# Timer-Ruler_v2.net
KiCad netlist of a schematic drawn in EAGLE
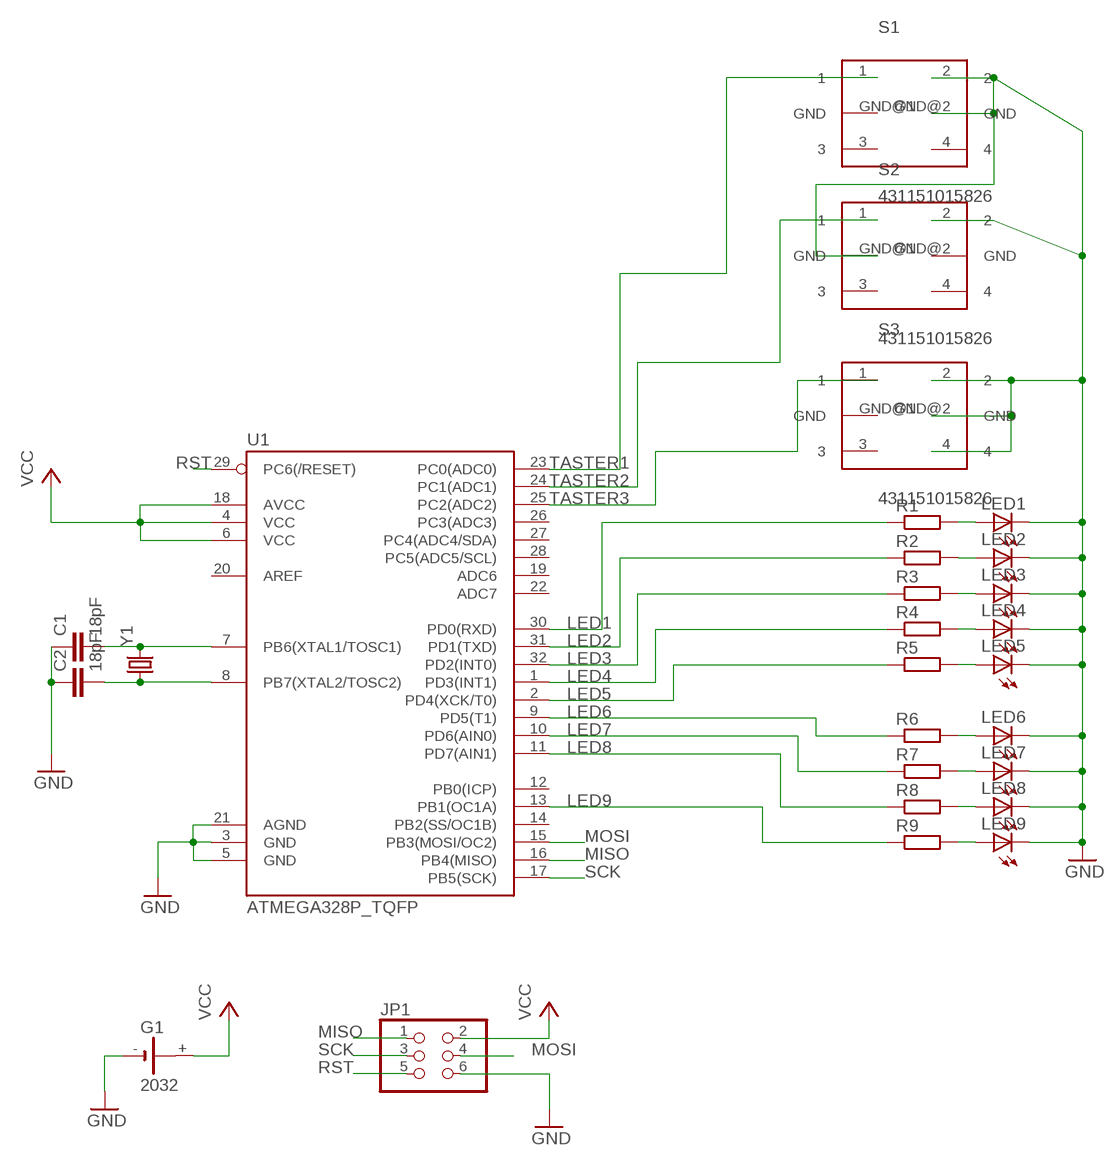
[diagram p0: schematic, sheet 1]

(export (version "E")
  (design (tool "Eeschema 10.0.6"))
  (components
    (comp (ref "C1")
      (value "18pF")
      (footprint "eagle-import:C0805K")
      (libsource (lib "eagle-import") (part "C-EUC0805K"))
    )
    (comp (ref "C2")
      (value "18pF")
      (footprint "eagle-import:C0805K")
      (libsource (lib "eagle-import") (part "C-EUC0805K"))
    )
    (comp (ref "G1")
      (value "2032")
      (footprint "eagle-import:KZH20SMD")
      (libsource (lib "eagle-import") (part "2032"))
    )
    (comp (ref "JP1")
      (value "PINHD-2X3")
      (footprint "eagle-import:2X03")
      (libsource (lib "eagle-import") (part "PINHD-2X3"))
    )
    (comp (ref "LED1")
      (value "LEDCHIP-LED0805")
      (footprint "eagle-import:CHIP-LED0805")
      (libsource (lib "eagle-import") (part "LEDCHIP-LED0805"))
    )
    (comp (ref "LED2")
      (value "LEDCHIP-LED0805")
      (footprint "eagle-import:CHIP-LED0805")
      (libsource (lib "eagle-import") (part "LEDCHIP-LED0805"))
    )
    (comp (ref "LED3")
      (value "LEDCHIP-LED0805")
      (footprint "eagle-import:CHIP-LED0805")
      (libsource (lib "eagle-import") (part "LEDCHIP-LED0805"))
    )
    (comp (ref "LED4")
      (value "LEDCHIP-LED0805")
      (footprint "eagle-import:CHIP-LED0805")
      (libsource (lib "eagle-import") (part "LEDCHIP-LED0805"))
    )
    (comp (ref "LED5")
      (value "LEDCHIP-LED0805")
      (footprint "eagle-import:CHIP-LED0805")
      (libsource (lib "eagle-import") (part "LEDCHIP-LED0805"))
    )
    (comp (ref "LED6")
      (value "LEDCHIP-LED0805")
      (footprint "eagle-import:CHIP-LED0805")
      (libsource (lib "eagle-import") (part "LEDCHIP-LED0805"))
    )
    (comp (ref "LED7")
      (value "LEDCHIP-LED0805")
      (footprint "eagle-import:CHIP-LED0805")
      (libsource (lib "eagle-import") (part "LEDCHIP-LED0805"))
    )
    (comp (ref "LED8")
      (value "LEDCHIP-LED0805")
      (footprint "eagle-import:CHIP-LED0805")
      (libsource (lib "eagle-import") (part "LEDCHIP-LED0805"))
    )
    (comp (ref "LED9")
      (value "LEDCHIP-LED0805")
      (footprint "eagle-import:CHIP-LED0805")
      (libsource (lib "eagle-import") (part "LEDCHIP-LED0805"))
    )
    (comp (ref "R1")
      (value "R-EU_R0805")
      (footprint "eagle-import:R0805")
      (libsource (lib "eagle-import") (part "R-EU_R0805"))
    )
    (comp (ref "R2")
      (value "R-EU_R0805")
      (footprint "eagle-import:R0805")
      (libsource (lib "eagle-import") (part "R-EU_R0805"))
    )
    (comp (ref "R3")
      (value "R-EU_R0805")
      (footprint "eagle-import:R0805")
      (libsource (lib "eagle-import") (part "R-EU_R0805"))
    )
    (comp (ref "R4")
      (value "R-EU_R0805")
      (footprint "eagle-import:R0805")
      (libsource (lib "eagle-import") (part "R-EU_R0805"))
    )
    (comp (ref "R5")
      (value "R-EU_R0805")
      (footprint "eagle-import:R0805")
      (libsource (lib "eagle-import") (part "R-EU_R0805"))
    )
    (comp (ref "R6")
      (value "R-EU_R0805")
      (footprint "eagle-import:R0805")
      (libsource (lib "eagle-import") (part "R-EU_R0805"))
    )
    (comp (ref "R7")
      (value "R-EU_R0805")
      (footprint "eagle-import:R0805")
      (libsource (lib "eagle-import") (part "R-EU_R0805"))
    )
    (comp (ref "R8")
      (value "R-EU_R0805")
      (footprint "eagle-import:R0805")
      (libsource (lib "eagle-import") (part "R-EU_R0805"))
    )
    (comp (ref "R9")
      (value "R-EU_R0805")
      (footprint "eagle-import:R0805")
      (libsource (lib "eagle-import") (part "R-EU_R0805"))
    )
    (comp (ref "S1")
      (value "431151015826")
      (footprint "eagle-import:431181015816")
      (libsource (lib "eagle-import") (part "431151015826"))
    )
    (comp (ref "S2")
      (value "431151015826")
      (footprint "eagle-import:431181015816")
      (libsource (lib "eagle-import") (part "431151015826"))
    )
    (comp (ref "S3")
      (value "431151015826")
      (footprint "eagle-import:431181015816")
      (libsource (lib "eagle-import") (part "431151015826"))
    )
    (comp (ref "U1")
      (value "ATMEGA328P_TQFP")
      (footprint "eagle-import:TQFP32-08")
      (libsource (lib "eagle-import") (part "ATMEGA328P_TQFP"))
    )
    (comp (ref "Y1")
      (value "CRYSTALSMD")
      (footprint "eagle-import:HC49UP")
      (libsource (lib "eagle-import") (part "CRYSTALSMD"))
    )
  )
  (nets
    (net (code "1") (name "/LED1") (class "Default")
      (node (ref "R1") (pin "1") (pinfunction "1_1") (pintype "passive"))
      (node (ref "U1") (pin "30") (pinfunction "PD0(RXD)_30") (pintype "bidirectional"))
    )
    (net (code "2") (name "/LED2") (class "Default")
      (node (ref "R2") (pin "1") (pinfunction "1_1") (pintype "passive"))
      (node (ref "U1") (pin "31") (pinfunction "PD1(TXD)_31") (pintype "bidirectional"))
    )
    (net (code "3") (name "/LED3") (class "Default")
      (node (ref "R3") (pin "1") (pinfunction "1_1") (pintype "passive"))
      (node (ref "U1") (pin "32") (pinfunction "PD2(INT0)_32") (pintype "bidirectional"))
    )
    (net (code "4") (name "/LED4") (class "Default")
      (node (ref "R4") (pin "1") (pinfunction "1_1") (pintype "passive"))
      (node (ref "U1") (pin "1") (pinfunction "PD3(INT1)_1") (pintype "bidirectional"))
    )
    (net (code "5") (name "/LED5") (class "Default")
      (node (ref "R5") (pin "1") (pinfunction "1_1") (pintype "passive"))
      (node (ref "U1") (pin "2") (pinfunction "PD4(XCK/T0)_2") (pintype "bidirectional"))
    )
    (net (code "6") (name "/LED6") (class "Default")
      (node (ref "R6") (pin "1") (pinfunction "1_1") (pintype "passive"))
      (node (ref "U1") (pin "9") (pinfunction "PD5(T1)_9") (pintype "bidirectional"))
    )
    (net (code "7") (name "/LED7") (class "Default")
      (node (ref "R7") (pin "1") (pinfunction "1_1") (pintype "passive"))
      (node (ref "U1") (pin "10") (pinfunction "PD6(AIN0)_10") (pintype "bidirectional"))
    )
    (net (code "8") (name "/LED8") (class "Default")
      (node (ref "R8") (pin "1") (pinfunction "1_1") (pintype "passive"))
      (node (ref "U1") (pin "11") (pinfunction "PD7(AIN1)_11") (pintype "bidirectional"))
    )
    (net (code "9") (name "/LED9") (class "Default")
      (node (ref "R9") (pin "1") (pinfunction "1_1") (pintype "passive"))
      (node (ref "U1") (pin "13") (pinfunction "PB1(OC1A)_13") (pintype "bidirectional"))
    )
    (net (code "10") (name "/MISO") (class "Default")
      (node (ref "JP1") (pin "1") (pinfunction "1_1") (pintype "passive"))
      (node (ref "U1") (pin "16") (pinfunction "PB4(MISO)_16") (pintype "bidirectional"))
    )
    (net (code "11") (name "/MOSI") (class "Default")
      (node (ref "JP1") (pin "4") (pinfunction "4_4") (pintype "passive"))
      (node (ref "U1") (pin "15") (pinfunction "PB3(MOSI/OC2)_15") (pintype "bidirectional"))
    )
    (net (code "12") (name "/RST") (class "Default")
      (node (ref "JP1") (pin "5") (pinfunction "5_5") (pintype "passive"))
      (node (ref "U1") (pin "29") (pinfunction "PC6(/RESET)_29") (pintype "bidirectional"))
    )
    (net (code "13") (name "/SCK") (class "Default")
      (node (ref "JP1") (pin "3") (pinfunction "3_3") (pintype "passive"))
      (node (ref "U1") (pin "17") (pinfunction "PB5(SCK)_17") (pintype "bidirectional"))
    )
    (net (code "14") (name "/TASTER1") (class "Default")
      (node (ref "S1") (pin "1") (pinfunction "1_1") (pintype "bidirectional"))
      (node (ref "U1") (pin "23") (pinfunction "PC0(ADC0)_23") (pintype "bidirectional"))
    )
    (net (code "15") (name "/TASTER2") (class "Default")
      (node (ref "S2") (pin "1") (pinfunction "1_1") (pintype "bidirectional"))
      (node (ref "U1") (pin "24") (pinfunction "PC1(ADC1)_24") (pintype "bidirectional"))
    )
    (net (code "16") (name "/TASTER3") (class "Default")
      (node (ref "S3") (pin "1") (pinfunction "1_1") (pintype "bidirectional"))
      (node (ref "U1") (pin "25") (pinfunction "PC2(ADC2)_25") (pintype "bidirectional"))
    )
    (net (code "17") (name "GND") (class "Default")
      (node (ref "C1") (pin "1") (pinfunction "1_1") (pintype "passive"))
      (node (ref "C2") (pin "1") (pinfunction "1_1") (pintype "passive"))
      (node (ref "G1") (pin "-") (pinfunction "-_-") (pintype "passive"))
      (node (ref "JP1") (pin "6") (pinfunction "6_6") (pintype "passive"))
      (node (ref "LED1") (pin "C") (pinfunction "C_C") (pintype "passive"))
      (node (ref "LED2") (pin "C") (pinfunction "C_C") (pintype "passive"))
      (node (ref "LED3") (pin "C") (pinfunction "C_C") (pintype "passive"))
      (node (ref "LED4") (pin "C") (pinfunction "C_C") (pintype "passive"))
      (node (ref "LED5") (pin "C") (pinfunction "C_C") (pintype "passive"))
      (node (ref "LED6") (pin "C") (pinfunction "C_C") (pintype "passive"))
      (node (ref "LED7") (pin "C") (pinfunction "C_C") (pintype "passive"))
      (node (ref "LED8") (pin "C") (pinfunction "C_C") (pintype "passive"))
      (node (ref "LED9") (pin "C") (pinfunction "C_C") (pintype "passive"))
      (node (ref "S1") (pin "2") (pinfunction "2_2") (pintype "bidirectional"))
      (node (ref "S1") (pin "GND@2") (pinfunction "GND_GND@2") (pintype "bidirectional"))
      (node (ref "S2") (pin "2") (pinfunction "2_2") (pintype "bidirectional"))
      (node (ref "S2") (pin "GND@1") (pinfunction "GND_GND@1") (pintype "bidirectional"))
      (node (ref "S3") (pin "2") (pinfunction "2_2") (pintype "bidirectional"))
      (node (ref "S3") (pin "4") (pinfunction "4_4") (pintype "bidirectional"))
      (node (ref "S3") (pin "GND@2") (pinfunction "GND_GND@2") (pintype "bidirectional"))
      (node (ref "U1") (pin "21") (pinfunction "AGND_21") (pintype "bidirectional"))
      (node (ref "U1") (pin "3") (pinfunction "GND_3") (pintype "bidirectional"))
      (node (ref "U1") (pin "5") (pinfunction "GND_5") (pintype "bidirectional"))
    )
    (net (code "18") (name "Net-(LED1-PadA)") (class "Default")
      (node (ref "LED1") (pin "A") (pinfunction "A_A") (pintype "passive"))
      (node (ref "R1") (pin "2") (pinfunction "2_2") (pintype "passive"))
    )
    (net (code "19") (name "Net-(LED2-PadA)") (class "Default")
      (node (ref "LED2") (pin "A") (pinfunction "A_A") (pintype "passive"))
      (node (ref "R2") (pin "2") (pinfunction "2_2") (pintype "passive"))
    )
    (net (code "20") (name "Net-(LED3-PadA)") (class "Default")
      (node (ref "LED3") (pin "A") (pinfunction "A_A") (pintype "passive"))
      (node (ref "R3") (pin "2") (pinfunction "2_2") (pintype "passive"))
    )
    (net (code "21") (name "Net-(LED4-PadA)") (class "Default")
      (node (ref "LED4") (pin "A") (pinfunction "A_A") (pintype "passive"))
      (node (ref "R4") (pin "2") (pinfunction "2_2") (pintype "passive"))
    )
    (net (code "22") (name "Net-(LED5-PadA)") (class "Default")
      (node (ref "LED5") (pin "A") (pinfunction "A_A") (pintype "passive"))
      (node (ref "R5") (pin "2") (pinfunction "2_2") (pintype "passive"))
    )
    (net (code "23") (name "Net-(LED6-PadA)") (class "Default")
      (node (ref "LED6") (pin "A") (pinfunction "A_A") (pintype "passive"))
      (node (ref "R6") (pin "2") (pinfunction "2_2") (pintype "passive"))
    )
    (net (code "24") (name "Net-(LED7-PadA)") (class "Default")
      (node (ref "LED7") (pin "A") (pinfunction "A_A") (pintype "passive"))
      (node (ref "R7") (pin "2") (pinfunction "2_2") (pintype "passive"))
    )
    (net (code "25") (name "Net-(LED8-PadA)") (class "Default")
      (node (ref "LED8") (pin "A") (pinfunction "A_A") (pintype "passive"))
      (node (ref "R8") (pin "2") (pinfunction "2_2") (pintype "passive"))
    )
    (net (code "26") (name "Net-(LED9-PadA)") (class "Default")
      (node (ref "LED9") (pin "A") (pinfunction "A_A") (pintype "passive"))
      (node (ref "R9") (pin "2") (pinfunction "2_2") (pintype "passive"))
    )
    (net (code "27") (name "Net-(U1-PB6(XTAL1{slash}TOSC1))") (class "Default")
      (node (ref "C1") (pin "2") (pinfunction "2_2") (pintype "passive"))
      (node (ref "U1") (pin "7") (pinfunction "PB6(XTAL1/TOSC1)_7") (pintype "bidirectional"))
      (node (ref "Y1") (pin "2") (pinfunction "2_2") (pintype "passive"))
    )
    (net (code "28") (name "Net-(U1-PB7(XTAL2{slash}TOSC2))") (class "Default")
      (node (ref "C2") (pin "2") (pinfunction "2_2") (pintype "passive"))
      (node (ref "U1") (pin "8") (pinfunction "PB7(XTAL2/TOSC2)_8") (pintype "bidirectional"))
      (node (ref "Y1") (pin "1") (pinfunction "1_1") (pintype "passive"))
    )
    (net (code "29") (name "VCC") (class "Default")
      (node (ref "G1") (pin "+") (pinfunction "+_+") (pintype "passive"))
      (node (ref "JP1") (pin "2") (pinfunction "2_2") (pintype "passive"))
      (node (ref "U1") (pin "18") (pinfunction "AVCC_18") (pintype "bidirectional"))
      (node (ref "U1") (pin "4") (pinfunction "VCC_4") (pintype "bidirectional"))
      (node (ref "U1") (pin "6") (pinfunction "VCC_6") (pintype "bidirectional"))
    )
    (net (code "30") (name "unconnected-(S1-GND-PadGND@1)") (class "Default")
      (node (ref "S1") (pin "GND@1") (pinfunction "GND_GND@1") (pintype "bidirectional"))
    )
    (net (code "31") (name "unconnected-(S1-Pad3)") (class "Default")
      (node (ref "S1") (pin "3") (pinfunction "3_3") (pintype "bidirectional"))
    )
    (net (code "32") (name "unconnected-(S1-Pad4)") (class "Default")
      (node (ref "S1") (pin "4") (pinfunction "4_4") (pintype "bidirectional"))
    )
    (net (code "33") (name "unconnected-(S2-GND-PadGND@2)") (class "Default")
      (node (ref "S2") (pin "GND@2") (pinfunction "GND_GND@2") (pintype "bidirectional"))
    )
    (net (code "34") (name "unconnected-(S2-Pad3)") (class "Default")
      (node (ref "S2") (pin "3") (pinfunction "3_3") (pintype "bidirectional"))
    )
    (net (code "35") (name "unconnected-(S2-Pad4)") (class "Default")
      (node (ref "S2") (pin "4") (pinfunction "4_4") (pintype "bidirectional"))
    )
    (net (code "36") (name "unconnected-(S3-GND-PadGND@1)") (class "Default")
      (node (ref "S3") (pin "GND@1") (pinfunction "GND_GND@1") (pintype "bidirectional"))
    )
    (net (code "37") (name "unconnected-(S3-Pad3)") (class "Default")
      (node (ref "S3") (pin "3") (pinfunction "3_3") (pintype "bidirectional"))
    )
    (net (code "38") (name "unconnected-(U1-ADC6-Pad19)") (class "Default")
      (node (ref "U1") (pin "19") (pinfunction "ADC6_19") (pintype "bidirectional"))
    )
    (net (code "39") (name "unconnected-(U1-ADC7-Pad22)") (class "Default")
      (node (ref "U1") (pin "22") (pinfunction "ADC7_22") (pintype "bidirectional"))
    )
    (net (code "40") (name "unconnected-(U1-AREF-Pad20)") (class "Default")
      (node (ref "U1") (pin "20") (pinfunction "AREF_20") (pintype "bidirectional"))
    )
    (net (code "41") (name "unconnected-(U1-PB0(ICP)-Pad12)") (class "Default")
      (node (ref "U1") (pin "12") (pinfunction "PB0(ICP)_12") (pintype "bidirectional"))
    )
    (net (code "42") (name "unconnected-(U1-PB2(SS{slash}OC1B)-Pad14)") (class "Default")
      (node (ref "U1") (pin "14") (pinfunction "PB2(SS/OC1B)_14") (pintype "bidirectional"))
    )
    (net (code "43") (name "unconnected-(U1-PC3(ADC3)-Pad26)") (class "Default")
      (node (ref "U1") (pin "26") (pinfunction "PC3(ADC3)_26") (pintype "bidirectional"))
    )
    (net (code "44") (name "unconnected-(U1-PC4(ADC4{slash}SDA)-Pad27)") (class "Default")
      (node (ref "U1") (pin "27") (pinfunction "PC4(ADC4/SDA)_27") (pintype "bidirectional"))
    )
    (net (code "45") (name "unconnected-(U1-PC5(ADC5{slash}SCL)-Pad28)") (class "Default")
      (node (ref "U1") (pin "28") (pinfunction "PC5(ADC5/SCL)_28") (pintype "bidirectional"))
    )
  )
)
